# design.net
KiCad netlist of a schematic drawn in Altium Designer
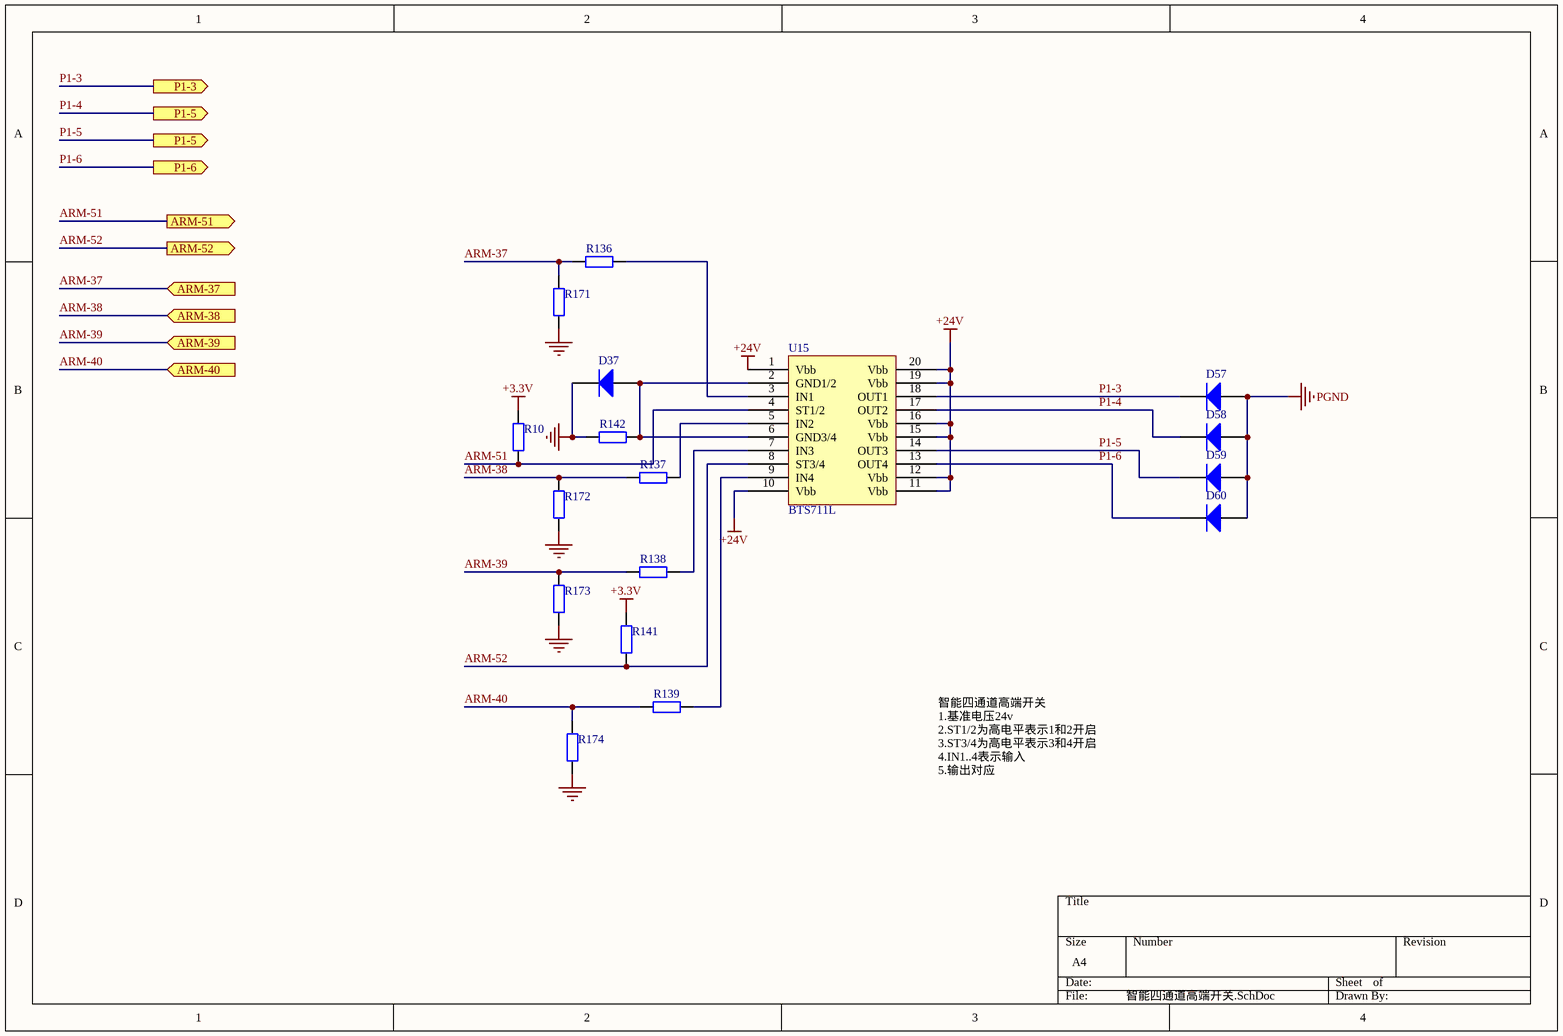
[diagram p0: 智能四通道高端开关.SchDoc]

(export (version "E")
  (design (tool "Eeschema 10.0.6"))
  (components
    (comp (ref "D37")
      (value "Diode 1N4007")
      (footprint "DO-41")
      (description "1 Amp General Purpose Rectifier")
      (fields (field (name "PUBLISHER") "Altium Limited"))
      (libsource (lib "Miscellaneous Devices") (part "Diode 1N4007"))
    )
    (comp (ref "D57")
      (value "Diode 1N4007")
      (footprint "DO-41")
      (description "1 Amp General Purpose Rectifier")
      (fields (field (name "PUBLISHER") "Altium Limited"))
      (libsource (lib "Miscellaneous Devices") (part "Diode 1N4007"))
    )
    (comp (ref "D58")
      (value "Diode 1N4007")
      (footprint "DO-41")
      (description "1 Amp General Purpose Rectifier")
      (fields (field (name "PUBLISHER") "Altium Limited"))
      (libsource (lib "Miscellaneous Devices") (part "Diode 1N4007"))
    )
    (comp (ref "D59")
      (value "Diode 1N4007")
      (footprint "DO-41")
      (description "1 Amp General Purpose Rectifier")
      (fields (field (name "PUBLISHER") "Altium Limited"))
      (libsource (lib "Miscellaneous Devices") (part "Diode 1N4007"))
    )
    (comp (ref "D60")
      (value "Diode 1N4007")
      (footprint "DO-41")
      (description "1 Amp General Purpose Rectifier")
      (fields (field (name "PUBLISHER") "Altium Limited"))
      (libsource (lib "Miscellaneous Devices") (part "Diode 1N4007"))
    )
    (comp (ref "R10")
      (value "Res2")
      (footprint "AXIAL-0.4")
      (description "Resistor")
      (fields (field (name "PUBLISHER") "Altium Limited"))
      (libsource (lib "") (part "Res2_1"))
    )
    (comp (ref "R136")
      (value "Res2")
      (footprint "AXIAL-0.4")
      (description "Resistor")
      (fields (field (name "PUBLISHER") "Altium Limited"))
      (libsource (lib "") (part "Res2_2"))
    )
    (comp (ref "R137")
      (value "Res2")
      (footprint "AXIAL-0.4")
      (description "Resistor")
      (fields (field (name "PUBLISHER") "Altium Limited"))
      (libsource (lib "") (part "Res2_2"))
    )
    (comp (ref "R138")
      (value "Res2")
      (footprint "AXIAL-0.4")
      (description "Resistor")
      (fields (field (name "PUBLISHER") "Altium Limited"))
      (libsource (lib "") (part "Res2_2"))
    )
    (comp (ref "R139")
      (value "Res2")
      (footprint "AXIAL-0.4")
      (description "Resistor")
      (fields (field (name "PUBLISHER") "Altium Limited"))
      (libsource (lib "Miscellaneous Devices") (part "Res2"))
    )
    (comp (ref "R141")
      (value "Res2")
      (footprint "AXIAL-0.4")
      (description "Resistor")
      (fields (field (name "PUBLISHER") "Altium Limited"))
      (libsource (lib "") (part "Res2_1"))
    )
    (comp (ref "R142")
      (value "Res2")
      (footprint "AXIAL-0.4")
      (description "Resistor")
      (fields (field (name "PUBLISHER") "Altium Limited"))
      (libsource (lib "") (part "Res2_2"))
    )
    (comp (ref "R171")
      (value "Res2")
      (footprint "AXIAL-0.4")
      (description "Resistor")
      (fields (field (name "PUBLISHER") "Altium Limited"))
      (libsource (lib "") (part "Res2_1"))
    )
    (comp (ref "R172")
      (value "Res2")
      (footprint "AXIAL-0.4")
      (description "Resistor")
      (fields (field (name "PUBLISHER") "Altium Limited"))
      (libsource (lib "") (part "Res2_1"))
    )
    (comp (ref "R173")
      (value "Res2")
      (footprint "AXIAL-0.4")
      (description "Resistor")
      (fields (field (name "PUBLISHER") "Altium Limited"))
      (libsource (lib "") (part "Res2_1"))
    )
    (comp (ref "R174")
      (value "Res2")
      (footprint "AXIAL-0.4")
      (description "Resistor")
      (fields (field (name "PUBLISHER") "Altium Limited"))
      (libsource (lib "") (part "Res2_1"))
    )
    (comp (ref "U15") (value "BTS711L") (libsource (lib "BTS711L1") (part "Component_1")))
  )
  (nets
    (net (code "1") (name "+3.3V") (class "Default")
      (node (ref "R10") (pin "2") (pinfunction "2_2") (pintype "passive"))
      (node (ref "R141") (pin "2") (pinfunction "2_2") (pintype "passive"))
    )
    (net (code "2") (name "+24V") (class "Default")
      (node (ref "U15") (pin "1") (pinfunction "Vbb_1") (pintype "passive"))
      (node (ref "U15") (pin "10") (pinfunction "Vbb_10") (pintype "passive"))
      (node (ref "U15") (pin "11") (pinfunction "Vbb_11") (pintype "passive"))
      (node (ref "U15") (pin "12") (pinfunction "Vbb_12") (pintype "passive"))
      (node (ref "U15") (pin "15") (pinfunction "Vbb_15") (pintype "passive"))
      (node (ref "U15") (pin "16") (pinfunction "Vbb_16") (pintype "passive"))
      (node (ref "U15") (pin "19") (pinfunction "Vbb_19") (pintype "passive"))
      (node (ref "U15") (pin "20") (pinfunction "Vbb_20") (pintype "passive"))
    )
    (net (code "3") (name "/ARM-37") (class "Default")
      (node (ref "R136") (pin "1") (pinfunction "1_1") (pintype "passive"))
      (node (ref "R171") (pin "2") (pinfunction "2_2") (pintype "passive"))
    )
    (net (code "4") (name "/ARM-38") (class "Default")
      (node (ref "R137") (pin "1") (pinfunction "1_1") (pintype "passive"))
      (node (ref "R172") (pin "2") (pinfunction "2_2") (pintype "passive"))
    )
    (net (code "5") (name "/ARM-39") (class "Default")
      (node (ref "R138") (pin "1") (pinfunction "1_1") (pintype "passive"))
      (node (ref "R173") (pin "2") (pinfunction "2_2") (pintype "passive"))
    )
    (net (code "6") (name "/ARM-40") (class "Default")
      (node (ref "R139") (pin "2") (pinfunction "2_2") (pintype "passive"))
      (node (ref "R174") (pin "2") (pinfunction "2_2") (pintype "passive"))
    )
    (net (code "7") (name "/ARM-51") (class "Default")
      (node (ref "R10") (pin "1") (pinfunction "1_1") (pintype "passive"))
      (node (ref "U15") (pin "4") (pinfunction "ST1/2_4") (pintype "passive"))
    )
    (net (code "8") (name "/ARM-52") (class "Default")
      (node (ref "R141") (pin "1") (pinfunction "1_1") (pintype "passive"))
      (node (ref "U15") (pin "8") (pinfunction "ST3/4_8") (pintype "passive"))
    )
    (net (code "9") (name "/P1-3") (class "Default")
      (node (ref "D57") (pin "2") (pinfunction "K_2") (pintype "passive"))
      (node (ref "U15") (pin "18") (pinfunction "OUT1_18") (pintype "passive"))
    )
    (net (code "10") (name "/P1-4") (class "Default")
      (node (ref "D58") (pin "2") (pinfunction "K_2") (pintype "passive"))
      (node (ref "D59") (pin "2") (pinfunction "K_2") (pintype "passive"))
      (node (ref "U15") (pin "14") (pinfunction "OUT3_14") (pintype "passive"))
      (node (ref "U15") (pin "17") (pinfunction "OUT2_17") (pintype "passive"))
    )
    (net (code "11") (name "/P1-6") (class "Default")
      (node (ref "D60") (pin "2") (pinfunction "K_2") (pintype "passive"))
      (node (ref "U15") (pin "13") (pinfunction "OUT4_13") (pintype "passive"))
    )
    (net (code "12") (name "GND") (class "Default")
      (node (ref "D37") (pin "2") (pinfunction "K_2") (pintype "passive"))
      (node (ref "R142") (pin "1") (pinfunction "1_1") (pintype "passive"))
      (node (ref "R171") (pin "1") (pinfunction "1_1") (pintype "passive"))
      (node (ref "R172") (pin "1") (pinfunction "1_1") (pintype "passive"))
      (node (ref "R173") (pin "1") (pinfunction "1_1") (pintype "passive"))
      (node (ref "R174") (pin "1") (pinfunction "1_1") (pintype "passive"))
    )
    (net (code "13") (name "Net-(D37-A)") (class "Default")
      (node (ref "D37") (pin "1") (pinfunction "A_1") (pintype "passive"))
      (node (ref "R142") (pin "2") (pinfunction "2_2") (pintype "passive"))
      (node (ref "U15") (pin "2") (pinfunction "GND1/2_2") (pintype "passive"))
      (node (ref "U15") (pin "6") (pinfunction "GND3/4_6") (pintype "passive"))
    )
    (net (code "14") (name "Net-(U15-IN1)") (class "Default")
      (node (ref "R136") (pin "2") (pinfunction "2_2") (pintype "passive"))
      (node (ref "U15") (pin "3") (pinfunction "IN1_3") (pintype "passive"))
    )
    (net (code "15") (name "Net-(U15-IN2)") (class "Default")
      (node (ref "R137") (pin "2") (pinfunction "2_2") (pintype "passive"))
      (node (ref "U15") (pin "5") (pinfunction "IN2_5") (pintype "passive"))
    )
    (net (code "16") (name "Net-(U15-IN3)") (class "Default")
      (node (ref "R138") (pin "2") (pinfunction "2_2") (pintype "passive"))
      (node (ref "U15") (pin "7") (pinfunction "IN3_7") (pintype "passive"))
    )
    (net (code "17") (name "Net-(U15-IN4)") (class "Default")
      (node (ref "R139") (pin "1") (pinfunction "1_1") (pintype "passive"))
      (node (ref "U15") (pin "9") (pinfunction "IN4_9") (pintype "passive"))
    )
    (net (code "18") (name "PGND") (class "Default")
      (node (ref "D57") (pin "1") (pinfunction "A_1") (pintype "passive"))
      (node (ref "D58") (pin "1") (pinfunction "A_1") (pintype "passive"))
      (node (ref "D59") (pin "1") (pinfunction "A_1") (pintype "passive"))
      (node (ref "D60") (pin "1") (pinfunction "A_1") (pintype "passive"))
    )
  )
)
